# 03_-_Power.net
KiCad netlist of a schematic drawn in Altium Designer
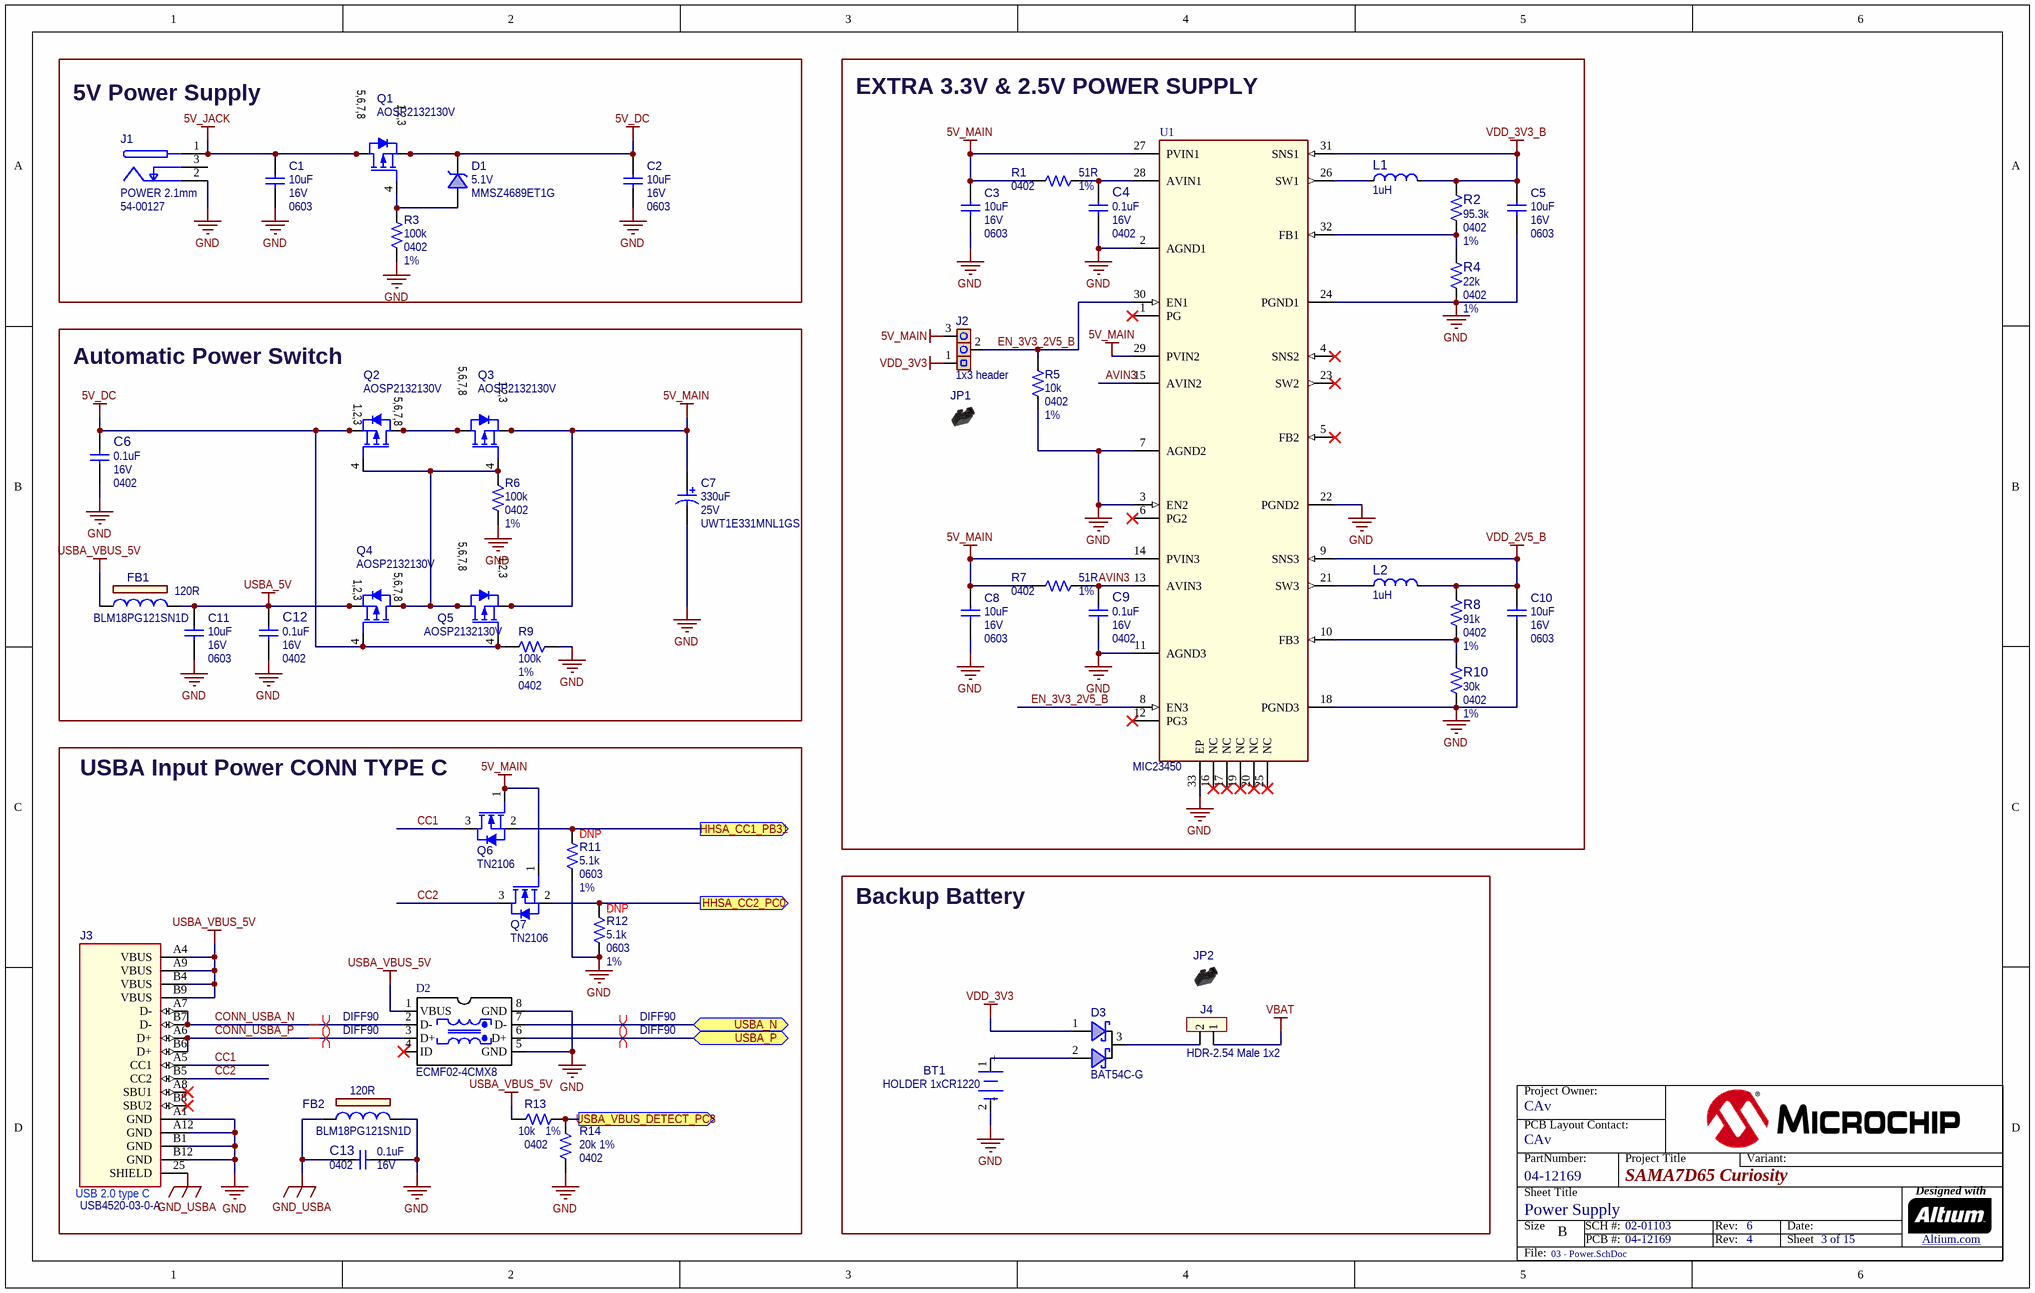
[diagram p0: 03 - Power.SchDoc]

(export (version "E")
  (design (tool "Eeschema 10.0.6"))
  (components
    (comp (ref "BT1")
      (value "HOLDER 1xCR1220")
      (footprint "BATT_HOLDER_12MM_3001")
      (description "Battery")
      (fields
        (field (name "VOLTAGE") "3V")
        (field (name "Comment") "Battery 2 Pin")
        (field (name "OWNER") "Sam Charles")
      )
      (libsource (lib "MCHP-CDB") (part "Battery 2 Pin"))
    )
    (comp (ref "C1")
      (value "10uF")
      (footprint "CAP_C_0603")
      (fields
        (field (name "VOLTAGE") "16V")
        (field (name "PACKAGE") "0603")
        (field (name "TOLERANCE") "10%")
        (field (name "Comment") "Capacitor NP")
        (field (name "OWNER") "Sam Charles")
      )
      (libsource (lib "MCHP-CDB") (part "Capacitor NP"))
    )
    (comp (ref "C2")
      (value "10uF")
      (footprint "CAP_C_0603")
      (fields
        (field (name "VOLTAGE") "16V")
        (field (name "PACKAGE") "0603")
        (field (name "TOLERANCE") "10%")
        (field (name "Comment") "Capacitor NP")
        (field (name "OWNER") "Sam Charles")
      )
      (libsource (lib "MCHP-CDB") (part "Capacitor NP"))
    )
    (comp (ref "C3")
      (value "10uF")
      (footprint "CAP_C_0603")
      (fields
        (field (name "VOLTAGE") "16V")
        (field (name "PACKAGE") "0603")
        (field (name "TOLERANCE") "10%")
        (field (name "Comment") "Capacitor NP")
        (field (name "OWNER") "Sam Charles")
      )
      (libsource (lib "MCHP-CDB") (part "Capacitor NP"))
    )
    (comp (ref "C4")
      (value "0.1uF")
      (footprint "CAP_C_0402")
      (fields
        (field (name "VOLTAGE") "16V")
        (field (name "PACKAGE") "0402")
        (field (name "TOLERANCE") "10%")
        (field (name "Comment") "Capacitor NP")
        (field (name "OWNER") "Sompoch Loboonlert")
      )
      (libsource (lib "MCHP-CDB") (part "Capacitor NP"))
    )
    (comp (ref "C5")
      (value "10uF")
      (footprint "CAP_C_0603")
      (fields
        (field (name "VOLTAGE") "16V")
        (field (name "PACKAGE") "0603")
        (field (name "TOLERANCE") "10%")
        (field (name "Comment") "Capacitor NP")
        (field (name "OWNER") "Sam Charles")
      )
      (libsource (lib "MCHP-CDB") (part "Capacitor NP"))
    )
    (comp (ref "C6")
      (value "0.1uF")
      (footprint "CAP_C_0402")
      (fields
        (field (name "VOLTAGE") "16V")
        (field (name "PACKAGE") "0402")
        (field (name "TOLERANCE") "10%")
        (field (name "Comment") "Capacitor NP")
        (field (name "OWNER") "Sompoch Loboonlert")
      )
      (libsource (lib "MCHP-CDB") (part "Capacitor NP"))
    )
    (comp (ref "C7")
      (value "330uF")
      (footprint "CAP_AL_F")
      (description "Capacitor")
      (fields
        (field (name "VOLTAGE") "25V")
        (field (name "TOLERANCE") "20%")
        (field (name "MANUFACTURER PART NUMBER 1") "UWT1E331MNL1GS")
        (field (name "Comment") "Capacitor POL")
      )
      (libsource (lib "MCHP-CDB") (part "Capacitor POL"))
    )
    (comp (ref "C8")
      (value "10uF")
      (footprint "CAP_C_0603")
      (fields
        (field (name "VOLTAGE") "16V")
        (field (name "PACKAGE") "0603")
        (field (name "TOLERANCE") "10%")
        (field (name "Comment") "Capacitor NP")
        (field (name "OWNER") "Sam Charles")
      )
      (libsource (lib "MCHP-CDB") (part "Capacitor NP"))
    )
    (comp (ref "C9")
      (value "0.1uF")
      (footprint "CAP_C_0402")
      (fields
        (field (name "VOLTAGE") "16V")
        (field (name "PACKAGE") "0402")
        (field (name "TOLERANCE") "10%")
        (field (name "Comment") "Capacitor NP")
        (field (name "OWNER") "Sompoch Loboonlert")
      )
      (libsource (lib "MCHP-CDB") (part "Capacitor NP"))
    )
    (comp (ref "C10")
      (value "10uF")
      (footprint "CAP_C_0603")
      (fields
        (field (name "VOLTAGE") "16V")
        (field (name "PACKAGE") "0603")
        (field (name "TOLERANCE") "10%")
        (field (name "Comment") "Capacitor NP")
        (field (name "OWNER") "Sam Charles")
      )
      (libsource (lib "MCHP-CDB") (part "Capacitor NP"))
    )
    (comp (ref "C11")
      (value "10uF")
      (footprint "CAP_C_0603")
      (fields
        (field (name "VOLTAGE") "16V")
        (field (name "PACKAGE") "0603")
        (field (name "TOLERANCE") "10%")
        (field (name "Comment") "Capacitor NP")
        (field (name "OWNER") "Sam Charles")
      )
      (libsource (lib "MCHP-CDB") (part "Capacitor NP"))
    )
    (comp (ref "C12")
      (value "0.1uF")
      (footprint "CAP_C_0402")
      (fields
        (field (name "VOLTAGE") "16V")
        (field (name "PACKAGE") "0402")
        (field (name "TOLERANCE") "10%")
        (field (name "Comment") "Capacitor NP")
        (field (name "OWNER") "Sompoch Loboonlert")
      )
      (libsource (lib "MCHP-CDB") (part "Capacitor NP"))
    )
    (comp (ref "C13")
      (value "0.1uF")
      (footprint "CAP_C_0402")
      (fields
        (field (name "VOLTAGE") "16V")
        (field (name "PACKAGE") "0402")
        (field (name "TOLERANCE") "10%")
        (field (name "Comment") "Capacitor NP")
        (field (name "OWNER") "Sompoch Loboonlert")
      )
      (libsource (lib "MCHP-CDB") (part "Capacitor NP"))
    )
    (comp (ref "D1")
      (value "5.1V")
      (footprint "SOD-123")
      (fields
        (field (name "POWER") "500mW")
        (field (name "MANUFACTURER PART NUMBER 1") "MMSZ4689ET1G")
        (field (name "Comment") "Diode Zener")
        (field (name "OWNER") "Cristian Papuc")
      )
      (libsource (lib "MCHP-CDB") (part "Diode Zener"))
    )
    (comp (ref "D2")
      (value "ECMF02-4CMX8")
      (footprint "DIODE ESD ECMF02-4CMX8")
      (description "IC ESD FILTER COMM MODE 8-UQFN")
      (fields (field (name "Comment") "ESD_ECMF02-4CMX8") (field (name "OWNER") "Dragos Danaila"))
      (libsource (lib "MCHP-CDB") (part "DIODE ESD ECMF02-4CMX8"))
    )
    (comp (ref "D3")
      (value "BAT54C-G")
      (footprint "SOT-23-3")
      (fields
        (field (name "POWER") "225mW")
        (field (name "Comment") "Diode Schottky Dual CK")
        (field (name "OWNER") "Cristina Salanti")
      )
      (libsource (lib "MCHP-CDB") (part "Diode Schottky Dual CK"))
    )
    (comp (ref "FB1")
      (value "120R")
      (footprint "IND_C_0603")
      (fields
        (field (name "MANUFACTURER PART NUMBER 1") "BLM18PG121SN1D")
        (field (name "Comment") "Ferrite Bead")
        (field (name "OWNER") "Petnarong Chaijaroong")
      )
      (libsource (lib "MCHP-CDB") (part "Ferrite Bead"))
    )
    (comp (ref "FB2")
      (value "120R")
      (footprint "IND_C_0603")
      (fields
        (field (name "MANUFACTURER PART NUMBER 1") "BLM18PG121SN1D")
        (field (name "Comment") "Ferrite Bead")
        (field (name "OWNER") "Petnarong Chaijaroong")
      )
      (libsource (lib "MCHP-CDB") (part "Ferrite Bead"))
    )
    (comp (ref "J1")
      (value "POWER 2.1mm")
      (footprint "CON_JACK_POWER_TH_RA_PJ-ID2.10 OD5.50")
      (fields
        (field (name "MANUFACTURER PART NUMBER 1") "54-00127")
        (field (name "VOLTAGE") "48V")
        (field (name "Comment") "CON JACK 2C 3P SPST")
        (field (name "OWNER") "Narasimha Murthy")
      )
      (libsource (lib "MCHP-CDB") (part "CON JACK 2C 3P SPST"))
    )
    (comp (ref "J2")
      (value "1x3 header")
      (footprint "HDR_M_2.54_1x3")
      (fields (field (name "Comment") "Header 1x3") (field (name "OWNER") "Dragos Danaila"))
      (libsource (lib "MCHP-CDB") (part "Header 1x3"))
    )
    (comp (ref "J3")
      (value "USB4520-03-0-A")
      (footprint "CON_USB2.0-C_SMD_RA_USB4520")
      (description "USB 2.0 type C connector")
      (fields
        (field (name "VOLTAGE") "20V")
        (field (name "Comment") "CON USB-2.0 C")
        (field (name "OWNER") "Ciprian Abramov")
      )
      (libsource (lib "MCHP-CDB") (part "CON USB2.0 C"))
    )
    (comp (ref "J4")
      (value "HDR-2.54 Male 1x2")
      (footprint "HDR_M_2.54_1x2")
      (fields
        (field (name "VOLTAGE") "250V")
        (field (name "Comment") "Header 1x2")
        (field (name "OWNER") "Narasimha Murthy")
      )
      (libsource (lib "MCHP-CDB") (part "Header 1x2"))
    )
    (comp (ref "JP1")
      (value "Jumper Mechanical")
      (footprint "Jumper_Mechanical")
      (fields (field (name "OWNER") "Narasimha Murthy"))
      (libsource (lib "MCHP-CDB") (part "Jumper Mechanical"))
    )
    (comp (ref "JP2")
      (value "Jumper Mechanical")
      (footprint "Jumper_Mechanical")
      (fields (field (name "OWNER") "Narasimha Murthy"))
      (libsource (lib "MCHP-CDB") (part "Jumper Mechanical"))
    )
    (comp (ref "L1")
      (value "1uH")
      (footprint "IND_C_1212")
      (description "Inductor")
      (fields (field (name "OWNER") "Cristina Salanti"))
      (libsource (lib "MCHP-CDB") (part "Inductor"))
    )
    (comp (ref "L2")
      (value "1uH")
      (footprint "IND_C_1212")
      (description "Inductor")
      (fields (field (name "OWNER") "Cristina Salanti"))
      (libsource (lib "MCHP-CDB") (part "Inductor"))
    )
    (comp (ref "Q1")
      (value "AOSP2132130V")
      (footprint "SOIC-8")
      (description "Transistor MOS")
      (fields
        (field (name "POWER") "3.1W")
        (field (name "Comment") "Transistor MOS-P SSSGDDDD")
        (field (name "OWNER") "Dragos Danaila")
      )
      (libsource (lib "MCHP-CDB") (part "Transistor MOS-P SSSGDDDD"))
    )
    (comp (ref "Q2")
      (value "AOSP2132130V")
      (footprint "SOIC-8")
      (description "Transistor MOS")
      (fields
        (field (name "POWER") "3.1W")
        (field (name "Comment") "Transistor MOS-P SSSGDDDD")
        (field (name "OWNER") "Dragos Danaila")
      )
      (libsource (lib "MCHP-CDB") (part "Transistor MOS-P SSSGDDDD"))
    )
    (comp (ref "Q3")
      (value "AOSP2132130V")
      (footprint "SOIC-8")
      (description "Transistor MOS")
      (fields
        (field (name "POWER") "3.1W")
        (field (name "Comment") "Transistor MOS-P SSSGDDDD")
        (field (name "OWNER") "Dragos Danaila")
      )
      (libsource (lib "MCHP-CDB") (part "Transistor MOS-P SSSGDDDD"))
    )
    (comp (ref "Q4")
      (value "AOSP2132130V")
      (footprint "SOIC-8")
      (description "Transistor MOS")
      (fields
        (field (name "POWER") "3.1W")
        (field (name "Comment") "Transistor MOS-P SSSGDDDD")
        (field (name "OWNER") "Dragos Danaila")
      )
      (libsource (lib "MCHP-CDB") (part "Transistor MOS-P SSSGDDDD"))
    )
    (comp (ref "Q5")
      (value "AOSP2132130V")
      (footprint "SOIC-8")
      (description "Transistor MOS")
      (fields
        (field (name "POWER") "3.1W")
        (field (name "Comment") "Transistor MOS-P SSSGDDDD")
        (field (name "OWNER") "Dragos Danaila")
      )
      (libsource (lib "MCHP-CDB") (part "Transistor MOS-P SSSGDDDD"))
    )
    (comp (ref "Q6")
      (value "TN2106")
      (footprint "SOT-23-3")
      (description "Transistor MOS")
      (fields (field (name "Comment") "Transistor MOS-N GSD") (field (name "OWNER") "Ilie Galan"))
      (libsource (lib "MCHP-CDB") (part "Transistor MOS-N GSD"))
    )
    (comp (ref "Q7")
      (value "TN2106")
      (footprint "SOT-23-3")
      (description "Transistor MOS")
      (fields (field (name "Comment") "Transistor MOS-N GSD") (field (name "OWNER") "Ilie Galan"))
      (libsource (lib "MCHP-CDB") (part "Transistor MOS-N GSD"))
    )
    (comp (ref "R1")
      (value "51R")
      (footprint "RES_C_0402")
      (description "Resistor")
      (fields
        (field (name "PACKAGE") "0402")
        (field (name "TOLERANCE") "1%")
        (field (name "VOLTAGE") "50V")
        (field (name "POWER") "1/5W")
        (field (name "OWNER") "Dragos Danaila")
      )
      (libsource (lib "MCHP-CDB") (part "Resistor"))
    )
    (comp (ref "R2")
      (value "95.3k")
      (footprint "RES_C_0402")
      (description "Resistor")
      (fields
        (field (name "PACKAGE") "0402")
        (field (name "TOLERANCE") "1%")
        (field (name "POWER") "1/16W")
        (field (name "OWNER") "Narasimha Murthy")
      )
      (libsource (lib "") (part "Resistor_1"))
    )
    (comp (ref "R3")
      (value "100k")
      (footprint "RES_C_0402")
      (description "Resistor")
      (fields
        (field (name "PACKAGE") "0402")
        (field (name "TOLERANCE") "1%")
        (field (name "VOLTAGE") "50V")
        (field (name "POWER") "1/10W")
        (field (name "OWNER") "Tad Ahlvers")
      )
      (libsource (lib "MCHP-CDB") (part "Resistor"))
    )
    (comp (ref "R4")
      (value "22k")
      (footprint "RES_C_0402")
      (description "Resistor")
      (fields
        (field (name "PACKAGE") "0402")
        (field (name "TOLERANCE") "1%")
        (field (name "VOLTAGE") "50V")
        (field (name "POWER") "1/10W")
        (field (name "OWNER") "Bogdan Popescu")
      )
      (libsource (lib "") (part "Resistor_1"))
    )
    (comp (ref "R5")
      (value "10k")
      (footprint "RES_C_0402")
      (description "Resistor")
      (fields
        (field (name "PACKAGE") "0402")
        (field (name "TOLERANCE") "1%")
        (field (name "VOLTAGE") "50V")
        (field (name "POWER") "1/10W")
        (field (name "OWNER") "Brent Lanphear")
      )
      (libsource (lib "MCHP-CDB") (part "Resistor"))
    )
    (comp (ref "R6")
      (value "100k")
      (footprint "RES_C_0402")
      (description "Resistor")
      (fields
        (field (name "PACKAGE") "0402")
        (field (name "TOLERANCE") "1%")
        (field (name "VOLTAGE") "50V")
        (field (name "POWER") "1/10W")
        (field (name "OWNER") "Tad Ahlvers")
      )
      (libsource (lib "MCHP-CDB") (part "Resistor"))
    )
    (comp (ref "R7")
      (value "51R")
      (footprint "RES_C_0402")
      (description "Resistor")
      (fields
        (field (name "PACKAGE") "0402")
        (field (name "TOLERANCE") "1%")
        (field (name "VOLTAGE") "50V")
        (field (name "POWER") "1/5W")
        (field (name "OWNER") "Dragos Danaila")
      )
      (libsource (lib "MCHP-CDB") (part "Resistor"))
    )
    (comp (ref "R8")
      (value "91k")
      (footprint "RES_C_0402")
      (description "Resistor")
      (fields
        (field (name "PACKAGE") "0402")
        (field (name "TOLERANCE") "1%")
        (field (name "VOLTAGE") "50V")
        (field (name "OWNER") "Octavian Stroe")
      )
      (libsource (lib "") (part "Resistor_1"))
    )
    (comp (ref "R9")
      (value "100k")
      (footprint "RES_C_0402")
      (description "Resistor")
      (fields
        (field (name "PACKAGE") "0402")
        (field (name "TOLERANCE") "1%")
        (field (name "VOLTAGE") "50V")
        (field (name "POWER") "1/10W")
        (field (name "OWNER") "Tad Ahlvers")
      )
      (libsource (lib "MCHP-CDB") (part "Resistor"))
    )
    (comp (ref "R10")
      (value "30k")
      (footprint "RES_C_0402")
      (description "Resistor")
      (fields
        (field (name "PACKAGE") "0402")
        (field (name "TOLERANCE") "1%")
        (field (name "VOLTAGE") "50V")
        (field (name "POWER") "1/10W")
        (field (name "OWNER") "Jennifer Hancock")
      )
      (libsource (lib "") (part "Resistor_1"))
    )
    (comp (ref "R11")
      (value "5.1k")
      (footprint "RES_C_0603")
      (description "Resistor")
      (fields
        (field (name "PACKAGE") "0603")
        (field (name "TOLERANCE") "1%")
        (field (name "VOLTAGE") "100V")
        (field (name "POWER") "1/10W")
        (field (name "POPULATED") "DNP")
        (field (name "OWNER") "Cristina Salanti")
      )
      (libsource (lib "") (part "Resistor_1"))
    )
    (comp (ref "R12")
      (value "5.1k")
      (footprint "RES_C_0603")
      (description "Resistor")
      (fields
        (field (name "PACKAGE") "0603")
        (field (name "TOLERANCE") "1%")
        (field (name "VOLTAGE") "100V")
        (field (name "POWER") "1/10W")
        (field (name "POPULATED") "DNP")
        (field (name "OWNER") "Cristina Salanti")
      )
      (libsource (lib "") (part "Resistor_1"))
    )
    (comp (ref "R13")
      (value "10k")
      (footprint "RES_C_0402")
      (description "Resistor")
      (fields
        (field (name "PACKAGE") "0402")
        (field (name "TOLERANCE") "1%")
        (field (name "POWER") "1/10W")
        (field (name "VOLTAGE") "50V")
        (field (name "OWNER") "Brent Lanphear")
      )
      (libsource (lib "MCHP-CDB") (part "Resistor"))
    )
    (comp (ref "R14")
      (value "20k")
      (footprint "RES_C_0402")
      (description "Resistor")
      (fields
        (field (name "PACKAGE") "0402")
        (field (name "TOLERANCE") "1%")
        (field (name "POWER") "1/16W")
        (field (name "VOLTAGE") "50V")
        (field (name "OWNER") "Dragos Danaila")
      )
      (libsource (lib "MCHP-CDB") (part "Resistor"))
    )
    (comp (ref "U1")
      (value "MIC23450")
      (footprint "QFN-32_5X5_EP3.1X3.1")
      (description "MIC23450 QFN-32")
      (fields (field (name "OWNER") "Razvan Cristescu"))
      (libsource (lib "MCHP-CDB") (part "MIC23450 QFN-32"))
    )
  )
  (nets
    (net (code "1") (name "/AVIN3") (class "Default")
      (node (ref "C9") (pin "2") (pinfunction "2_2") (pintype "passive"))
      (node (ref "R7") (pin "1") (pinfunction "1_1") (pintype "passive"))
      (node (ref "U1") (pin "13") (pinfunction "AVIN3_13") (pintype "power_in"))
      (node (ref "U1") (pin "15") (pinfunction "AVIN2_15") (pintype "power_in"))
    )
    (net (code "2") (name "/CC1") (class "Default")
      (node (ref "J3") (pin "A5") (pinfunction "CC1_A5") (pintype "bidirectional"))
      (node (ref "Q6") (pin "3") (pinfunction "D_3") (pintype "passive"))
    )
    (net (code "3") (name "/CC2") (class "Default")
      (node (ref "J3") (pin "B5") (pinfunction "CC2_B5") (pintype "bidirectional"))
      (node (ref "Q7") (pin "3") (pinfunction "D_3") (pintype "passive"))
    )
    (net (code "4") (name "/CONN_USBA_N") (class "Default")
      (node (ref "D2") (pin "2") (pinfunction "D-_2") (pintype "passive"))
      (node (ref "J3") (pin "A7") (pinfunction "D-_A7") (pintype "bidirectional"))
      (node (ref "J3") (pin "B7") (pinfunction "D-_B7") (pintype "bidirectional"))
    )
    (net (code "5") (name "/CONN_USBA_P") (class "Default")
      (node (ref "D2") (pin "3") (pinfunction "D+_3") (pintype "passive"))
      (node (ref "J3") (pin "A6") (pinfunction "D+_A6") (pintype "bidirectional"))
      (node (ref "J3") (pin "B6") (pinfunction "D+_B6") (pintype "bidirectional"))
    )
    (net (code "6") (name "/EN_3V3_2V5_B") (class "Default")
      (node (ref "J2") (pin "2") (pinfunction "2_2") (pintype "passive"))
      (node (ref "R5") (pin "2") (pinfunction "2_2") (pintype "passive"))
      (node (ref "U1") (pin "30") (pinfunction "EN1_30") (pintype "input"))
      (node (ref "U1") (pin "8") (pinfunction "EN3_8") (pintype "input"))
    )
    (net (code "7") (name "/HHSA_CC1_PB31") (class "Default")
      (node (ref "Q6") (pin "2") (pinfunction "S_2") (pintype "passive"))
      (node (ref "R11") (pin "1") (pinfunction "1_1") (pintype "passive"))
    )
    (net (code "8") (name "/HHSA_CC2_PC0") (class "Default")
      (node (ref "Q7") (pin "2") (pinfunction "S_2") (pintype "passive"))
      (node (ref "R12") (pin "1") (pinfunction "1_1") (pintype "passive"))
    )
    (net (code "9") (name "/USBA_N") (class "Default")
      (node (ref "D2") (pin "7") (pinfunction "D-_7") (pintype "passive"))
    )
    (net (code "10") (name "/USBA_P") (class "Default")
      (node (ref "D2") (pin "6") (pinfunction "D+_6") (pintype "passive"))
    )
    (net (code "11") (name "/USBA_VBUS_DETECT_PC8") (class "Default")
      (node (ref "R13") (pin "2") (pinfunction "2_2") (pintype "passive"))
      (node (ref "R14") (pin "2") (pinfunction "2_2") (pintype "passive"))
    )
    (net (code "12") (name "5V_DC") (class "Default")
      (node (ref "C2") (pin "1") (pinfunction "1_1") (pintype "passive"))
      (node (ref "C6") (pin "2") (pinfunction "2_2") (pintype "passive"))
      (node (ref "D1") (pin "2") (pinfunction "K_2") (pintype "passive"))
      (node (ref "Q1") (pin "1") (pinfunction "S_1") (pintype "passive"))
      (node (ref "Q1") (pin "2") (pinfunction "S_2") (pintype "passive"))
      (node (ref "Q1") (pin "3") (pinfunction "S_3") (pintype "passive"))
      (node (ref "Q2") (pin "1") (pinfunction "S_1") (pintype "passive"))
      (node (ref "Q2") (pin "2") (pinfunction "S_2") (pintype "passive"))
      (node (ref "Q2") (pin "3") (pinfunction "S_3") (pintype "passive"))
      (node (ref "Q4") (pin "4") (pinfunction "G_4") (pintype "passive"))
      (node (ref "Q5") (pin "4") (pinfunction "G_4") (pintype "passive"))
      (node (ref "R9") (pin "2") (pinfunction "2_2") (pintype "passive"))
    )
    (net (code "13") (name "5V_JACK") (class "Default")
      (node (ref "C1") (pin "1") (pinfunction "1_1") (pintype "passive"))
      (node (ref "J1") (pin "1") (pinfunction "PLUS_1") (pintype "passive"))
      (node (ref "Q1") (pin "5") (pinfunction "D_5") (pintype "passive"))
      (node (ref "Q1") (pin "6") (pinfunction "D_6") (pintype "passive"))
      (node (ref "Q1") (pin "7") (pinfunction "D_7") (pintype "passive"))
      (node (ref "Q1") (pin "8") (pinfunction "D_8") (pintype "passive"))
    )
    (net (code "14") (name "5V_MAIN") (class "Default")
      (node (ref "C3") (pin "1") (pinfunction "1_1") (pintype "passive"))
      (node (ref "C7") (pin "1") (pinfunction "1_1") (pintype "passive"))
      (node (ref "C8") (pin "1") (pinfunction "1_1") (pintype "passive"))
      (node (ref "J2") (pin "3") (pinfunction "3_3") (pintype "passive"))
      (node (ref "Q3") (pin "1") (pinfunction "S_1") (pintype "passive"))
      (node (ref "Q3") (pin "2") (pinfunction "S_2") (pintype "passive"))
      (node (ref "Q3") (pin "3") (pinfunction "S_3") (pintype "passive"))
      (node (ref "Q5") (pin "1") (pinfunction "S_1") (pintype "passive"))
      (node (ref "Q5") (pin "2") (pinfunction "S_2") (pintype "passive"))
      (node (ref "Q5") (pin "3") (pinfunction "S_3") (pintype "passive"))
      (node (ref "Q6") (pin "1") (pinfunction "G_1") (pintype "passive"))
      (node (ref "Q7") (pin "1") (pinfunction "G_1") (pintype "passive"))
      (node (ref "R1") (pin "2") (pinfunction "2_2") (pintype "passive"))
      (node (ref "R7") (pin "2") (pinfunction "2_2") (pintype "passive"))
      (node (ref "U1") (pin "14") (pinfunction "PVIN3_14") (pintype "power_in"))
      (node (ref "U1") (pin "27") (pinfunction "PVIN1_27") (pintype "power_in"))
      (node (ref "U1") (pin "29") (pinfunction "PVIN2_29") (pintype "power_in"))
    )
    (net (code "15") (name "GND") (class "Default")
      (node (ref "BT1") (pin "2") (pinfunction "-_2") (pintype "power_in"))
      (node (ref "C1") (pin "2") (pinfunction "2_2") (pintype "passive"))
      (node (ref "C10") (pin "2") (pinfunction "2_2") (pintype "passive"))
      (node (ref "C11") (pin "2") (pinfunction "2_2") (pintype "passive"))
      (node (ref "C12") (pin "1") (pinfunction "1_1") (pintype "passive"))
      (node (ref "C13") (pin "2") (pinfunction "2_2") (pintype "passive"))
      (node (ref "C2") (pin "2") (pinfunction "2_2") (pintype "passive"))
      (node (ref "C3") (pin "2") (pinfunction "2_2") (pintype "passive"))
      (node (ref "C4") (pin "1") (pinfunction "1_1") (pintype "passive"))
      (node (ref "C5") (pin "2") (pinfunction "2_2") (pintype "passive"))
      (node (ref "C6") (pin "1") (pinfunction "1_1") (pintype "passive"))
      (node (ref "C7") (pin "2") (pinfunction "2_2") (pintype "passive"))
      (node (ref "C8") (pin "2") (pinfunction "2_2") (pintype "passive"))
      (node (ref "C9") (pin "1") (pinfunction "1_1") (pintype "passive"))
      (node (ref "D2") (pin "5") (pinfunction "GND_5") (pintype "passive"))
      (node (ref "D2") (pin "8") (pinfunction "GND_8") (pintype "passive"))
      (node (ref "FB2") (pin "2") (pinfunction "2_2") (pintype "passive"))
      (node (ref "J1") (pin "2") (pinfunction "COM_2") (pintype "passive"))
      (node (ref "J3") (pin "A1") (pinfunction "GND_A1") (pintype "power_in"))
      (node (ref "J3") (pin "A12") (pinfunction "GND_A12") (pintype "power_in"))
      (node (ref "J3") (pin "B1") (pinfunction "GND_B1") (pintype "power_in"))
      (node (ref "J3") (pin "B12") (pinfunction "GND_B12") (pintype "power_in"))
      (node (ref "R10") (pin "1") (pinfunction "1_1") (pintype "passive"))
      (node (ref "R11") (pin "2") (pinfunction "2_2") (pintype "passive"))
      (node (ref "R12") (pin "2") (pinfunction "2_2") (pintype "passive"))
      (node (ref "R14") (pin "1") (pinfunction "1_1") (pintype "passive"))
      (node (ref "R3") (pin "1") (pinfunction "1_1") (pintype "passive"))
      (node (ref "R4") (pin "1") (pinfunction "1_1") (pintype "passive"))
      (node (ref "R5") (pin "1") (pinfunction "1_1") (pintype "passive"))
      (node (ref "R6") (pin "1") (pinfunction "1_1") (pintype "passive"))
      (node (ref "R9") (pin "1") (pinfunction "1_1") (pintype "passive"))
      (node (ref "U1") (pin "11") (pinfunction "AGND3_11") (pintype "power_in"))
      (node (ref "U1") (pin "18") (pinfunction "PGND3_18") (pintype "power_in"))
      (node (ref "U1") (pin "2") (pinfunction "AGND1_2") (pintype "power_in"))
      (node (ref "U1") (pin "22") (pinfunction "PGND2_22") (pintype "power_in"))
      (node (ref "U1") (pin "24") (pinfunction "PGND1_24") (pintype "power_in"))
      (node (ref "U1") (pin "3") (pinfunction "EN2_3") (pintype "input"))
      (node (ref "U1") (pin "33") (pinfunction "EP_33") (pintype "power_in"))
      (node (ref "U1") (pin "7") (pinfunction "AGND2_7") (pintype "power_in"))
    )
    (net (code "16") (name "GND_USBA") (class "Default")
      (node (ref "C13") (pin "1") (pinfunction "1_1") (pintype "passive"))
      (node (ref "FB2") (pin "1") (pinfunction "1_1") (pintype "passive"))
      (node (ref "J3") (pin "25") (pinfunction "SHIELD_25") (pintype "power_in"))
    )
    (net (code "17") (name "Net-(BT1-+)") (class "Default")
      (node (ref "BT1") (pin "1") (pinfunction "+_1") (pintype "power_in"))
      (node (ref "D3") (pin "2") (pinfunction "A_2") (pintype "passive"))
    )
    (net (code "18") (name "Net-(D1-A)") (class "Default")
      (node (ref "D1") (pin "1") (pinfunction "A_1") (pintype "passive"))
      (node (ref "Q1") (pin "4") (pinfunction "G_4") (pintype "passive"))
      (node (ref "R3") (pin "2") (pinfunction "2_2") (pintype "passive"))
    )
    (net (code "19") (name "Net-(D3-KK)") (class "Default")
      (node (ref "D3") (pin "3") (pinfunction "KK_3") (pintype "passive"))
      (node (ref "J4") (pin "2") (pinfunction "2_2") (pintype "passive"))
    )
    (net (code "20") (name "Net-(L1-S)") (class "Default")
      (node (ref "L1") (pin "1") (pinfunction "S_1") (pintype "passive"))
      (node (ref "U1") (pin "26") (pinfunction "SW1_26") (pintype "output"))
    )
    (net (code "21") (name "Net-(L2-S)") (class "Default")
      (node (ref "L2") (pin "1") (pinfunction "S_1") (pintype "passive"))
      (node (ref "U1") (pin "21") (pinfunction "SW3_21") (pintype "output"))
    )
    (net (code "22") (name "Net-(Q2-D-Pad5)") (class "Default")
      (node (ref "Q2") (pin "5") (pinfunction "D_5") (pintype "passive"))
      (node (ref "Q2") (pin "6") (pinfunction "D_6") (pintype "passive"))
      (node (ref "Q2") (pin "7") (pinfunction "D_7") (pintype "passive"))
      (node (ref "Q2") (pin "8") (pinfunction "D_8") (pintype "passive"))
      (node (ref "Q3") (pin "5") (pinfunction "D_5") (pintype "passive"))
      (node (ref "Q3") (pin "6") (pinfunction "D_6") (pintype "passive"))
      (node (ref "Q3") (pin "7") (pinfunction "D_7") (pintype "passive"))
      (node (ref "Q3") (pin "8") (pinfunction "D_8") (pintype "passive"))
    )
    (net (code "23") (name "Net-(Q2-G)") (class "Default")
      (node (ref "Q2") (pin "4") (pinfunction "G_4") (pintype "passive"))
      (node (ref "Q3") (pin "4") (pinfunction "G_4") (pintype "passive"))
      (node (ref "Q4") (pin "5") (pinfunction "D_5") (pintype "passive"))
      (node (ref "Q4") (pin "6") (pinfunction "D_6") (pintype "passive"))
      (node (ref "Q4") (pin "7") (pinfunction "D_7") (pintype "passive"))
      (node (ref "Q4") (pin "8") (pinfunction "D_8") (pintype "passive"))
      (node (ref "Q5") (pin "5") (pinfunction "D_5") (pintype "passive"))
      (node (ref "Q5") (pin "6") (pinfunction "D_6") (pintype "passive"))
      (node (ref "Q5") (pin "7") (pinfunction "D_7") (pintype "passive"))
      (node (ref "Q5") (pin "8") (pinfunction "D_8") (pintype "passive"))
      (node (ref "R6") (pin "2") (pinfunction "2_2") (pintype "passive"))
    )
    (net (code "24") (name "Net-(U1-AVIN1)") (class "Default")
      (node (ref "C4") (pin "2") (pinfunction "2_2") (pintype "passive"))
      (node (ref "R1") (pin "1") (pinfunction "1_1") (pintype "passive"))
      (node (ref "U1") (pin "28") (pinfunction "AVIN1_28") (pintype "power_in"))
    )
    (net (code "25") (name "Net-(U1-FB1)") (class "Default")
      (node (ref "R2") (pin "2") (pinfunction "2_2") (pintype "passive"))
      (node (ref "R4") (pin "2") (pinfunction "2_2") (pintype "passive"))
      (node (ref "U1") (pin "32") (pinfunction "FB1_32") (pintype "input"))
    )
    (net (code "26") (name "Net-(U1-FB3)") (class "Default")
      (node (ref "R10") (pin "2") (pinfunction "2_2") (pintype "passive"))
      (node (ref "R8") (pin "2") (pinfunction "2_2") (pintype "passive"))
      (node (ref "U1") (pin "10") (pinfunction "FB3_10") (pintype "input"))
    )
    (net (code "27") (name "USBA_5V") (class "Default")
      (node (ref "C11") (pin "1") (pinfunction "1_1") (pintype "passive"))
      (node (ref "C12") (pin "2") (pinfunction "2_2") (pintype "passive"))
      (node (ref "FB1") (pin "2") (pinfunction "2_2") (pintype "passive"))
      (node (ref "Q4") (pin "1") (pinfunction "S_1") (pintype "passive"))
      (node (ref "Q4") (pin "2") (pinfunction "S_2") (pintype "passive"))
      (node (ref "Q4") (pin "3") (pinfunction "S_3") (pintype "passive"))
    )
    (net (code "28") (name "USBA_VBUS_5V") (class "Default")
      (node (ref "D2") (pin "1") (pinfunction "VBUS_1") (pintype "passive"))
      (node (ref "FB1") (pin "1") (pinfunction "1_1") (pintype "passive"))
      (node (ref "J3") (pin "A4") (pinfunction "VBUS_A4") (pintype "power_in"))
      (node (ref "J3") (pin "A9") (pinfunction "VBUS_A9") (pintype "power_in"))
      (node (ref "J3") (pin "B4") (pinfunction "VBUS_B4") (pintype "power_in"))
      (node (ref "J3") (pin "B9") (pinfunction "VBUS_B9") (pintype "power_in"))
      (node (ref "R13") (pin "1") (pinfunction "1_1") (pintype "passive"))
    )
    (net (code "29") (name "VBAT") (class "Default")
      (node (ref "J4") (pin "1") (pinfunction "1_1") (pintype "passive"))
    )
    (net (code "30") (name "VDD_2V5_B") (class "Default")
      (node (ref "C10") (pin "1") (pinfunction "1_1") (pintype "passive"))
      (node (ref "L2") (pin "2") (pinfunction "F_2") (pintype "passive"))
      (node (ref "R8") (pin "1") (pinfunction "1_1") (pintype "passive"))
      (node (ref "U1") (pin "9") (pinfunction "SNS3_9") (pintype "input"))
    )
    (net (code "31") (name "VDD_3V3") (class "Default")
      (node (ref "D3") (pin "1") (pinfunction "A_1") (pintype "passive"))
      (node (ref "J2") (pin "1") (pinfunction "1_1") (pintype "passive"))
    )
    (net (code "32") (name "VDD_3V3_B") (class "Default")
      (node (ref "C5") (pin "1") (pinfunction "1_1") (pintype "passive"))
      (node (ref "L1") (pin "2") (pinfunction "F_2") (pintype "passive"))
      (node (ref "R2") (pin "1") (pinfunction "1_1") (pintype "passive"))
      (node (ref "U1") (pin "31") (pinfunction "SNS1_31") (pintype "input"))
    )
    (net (code "33") (name "unconnected-(D2-ID-Pad4)") (class "Default")
      (node (ref "D2") (pin "4") (pinfunction "ID_4") (pintype "passive+no_connect"))
    )
    (net (code "34") (name "unconnected-(J1-SWITCH-Pad3)") (class "Default")
      (node (ref "J1") (pin "3") (pinfunction "SWITCH_3") (pintype "passive"))
    )
    (net (code "35") (name "unconnected-(J3-SBU1-PadA8)") (class "Default")
      (node (ref "J3") (pin "A8") (pinfunction "SBU1_A8") (pintype "bidirectional+no_connect"))
    )
    (net (code "36") (name "unconnected-(J3-SBU2-PadB8)") (class "Default")
      (node (ref "J3") (pin "B8") (pinfunction "SBU2_B8") (pintype "bidirectional+no_connect"))
    )
    (net (code "37") (name "unconnected-(U1-FB2-Pad5)") (class "Default")
      (node (ref "U1") (pin "5") (pinfunction "FB2_5") (pintype "input+no_connect"))
    )
    (net (code "38") (name "unconnected-(U1-NC-Pad16)") (class "Default")
      (node (ref "U1") (pin "16") (pinfunction "NC_16") (pintype "passive+no_connect"))
    )
    (net (code "39") (name "unconnected-(U1-NC-Pad17)") (class "Default")
      (node (ref "U1") (pin "17") (pinfunction "NC_17") (pintype "passive+no_connect"))
    )
    (net (code "40") (name "unconnected-(U1-NC-Pad19)") (class "Default")
      (node (ref "U1") (pin "19") (pinfunction "NC_19") (pintype "passive+no_connect"))
    )
    (net (code "41") (name "unconnected-(U1-NC-Pad20)") (class "Default")
      (node (ref "U1") (pin "20") (pinfunction "NC_20") (pintype "passive+no_connect"))
    )
    (net (code "42") (name "unconnected-(U1-NC-Pad25)") (class "Default")
      (node (ref "U1") (pin "25") (pinfunction "NC_25") (pintype "passive+no_connect"))
    )
    (net (code "43") (name "unconnected-(U1-PG-Pad1)") (class "Default")
      (node (ref "U1") (pin "1") (pinfunction "PG_1") (pintype "power_in+no_connect"))
    )
    (net (code "44") (name "unconnected-(U1-PG2-Pad6)") (class "Default")
      (node (ref "U1") (pin "6") (pinfunction "PG2_6") (pintype "power_in+no_connect"))
    )
    (net (code "45") (name "unconnected-(U1-PG3-Pad12)") (class "Default")
      (node (ref "U1") (pin "12") (pinfunction "PG3_12") (pintype "power_in+no_connect"))
    )
    (net (code "46") (name "unconnected-(U1-SNS2-Pad4)") (class "Default")
      (node (ref "U1") (pin "4") (pinfunction "SNS2_4") (pintype "input+no_connect"))
    )
    (net (code "47") (name "unconnected-(U1-SW2-Pad23)") (class "Default")
      (node (ref "U1") (pin "23") (pinfunction "SW2_23") (pintype "output+no_connect"))
    )
  )
)
